# hamilton-thermostat-main.net
KiCad netlist of a schematic drawn in EAGLE
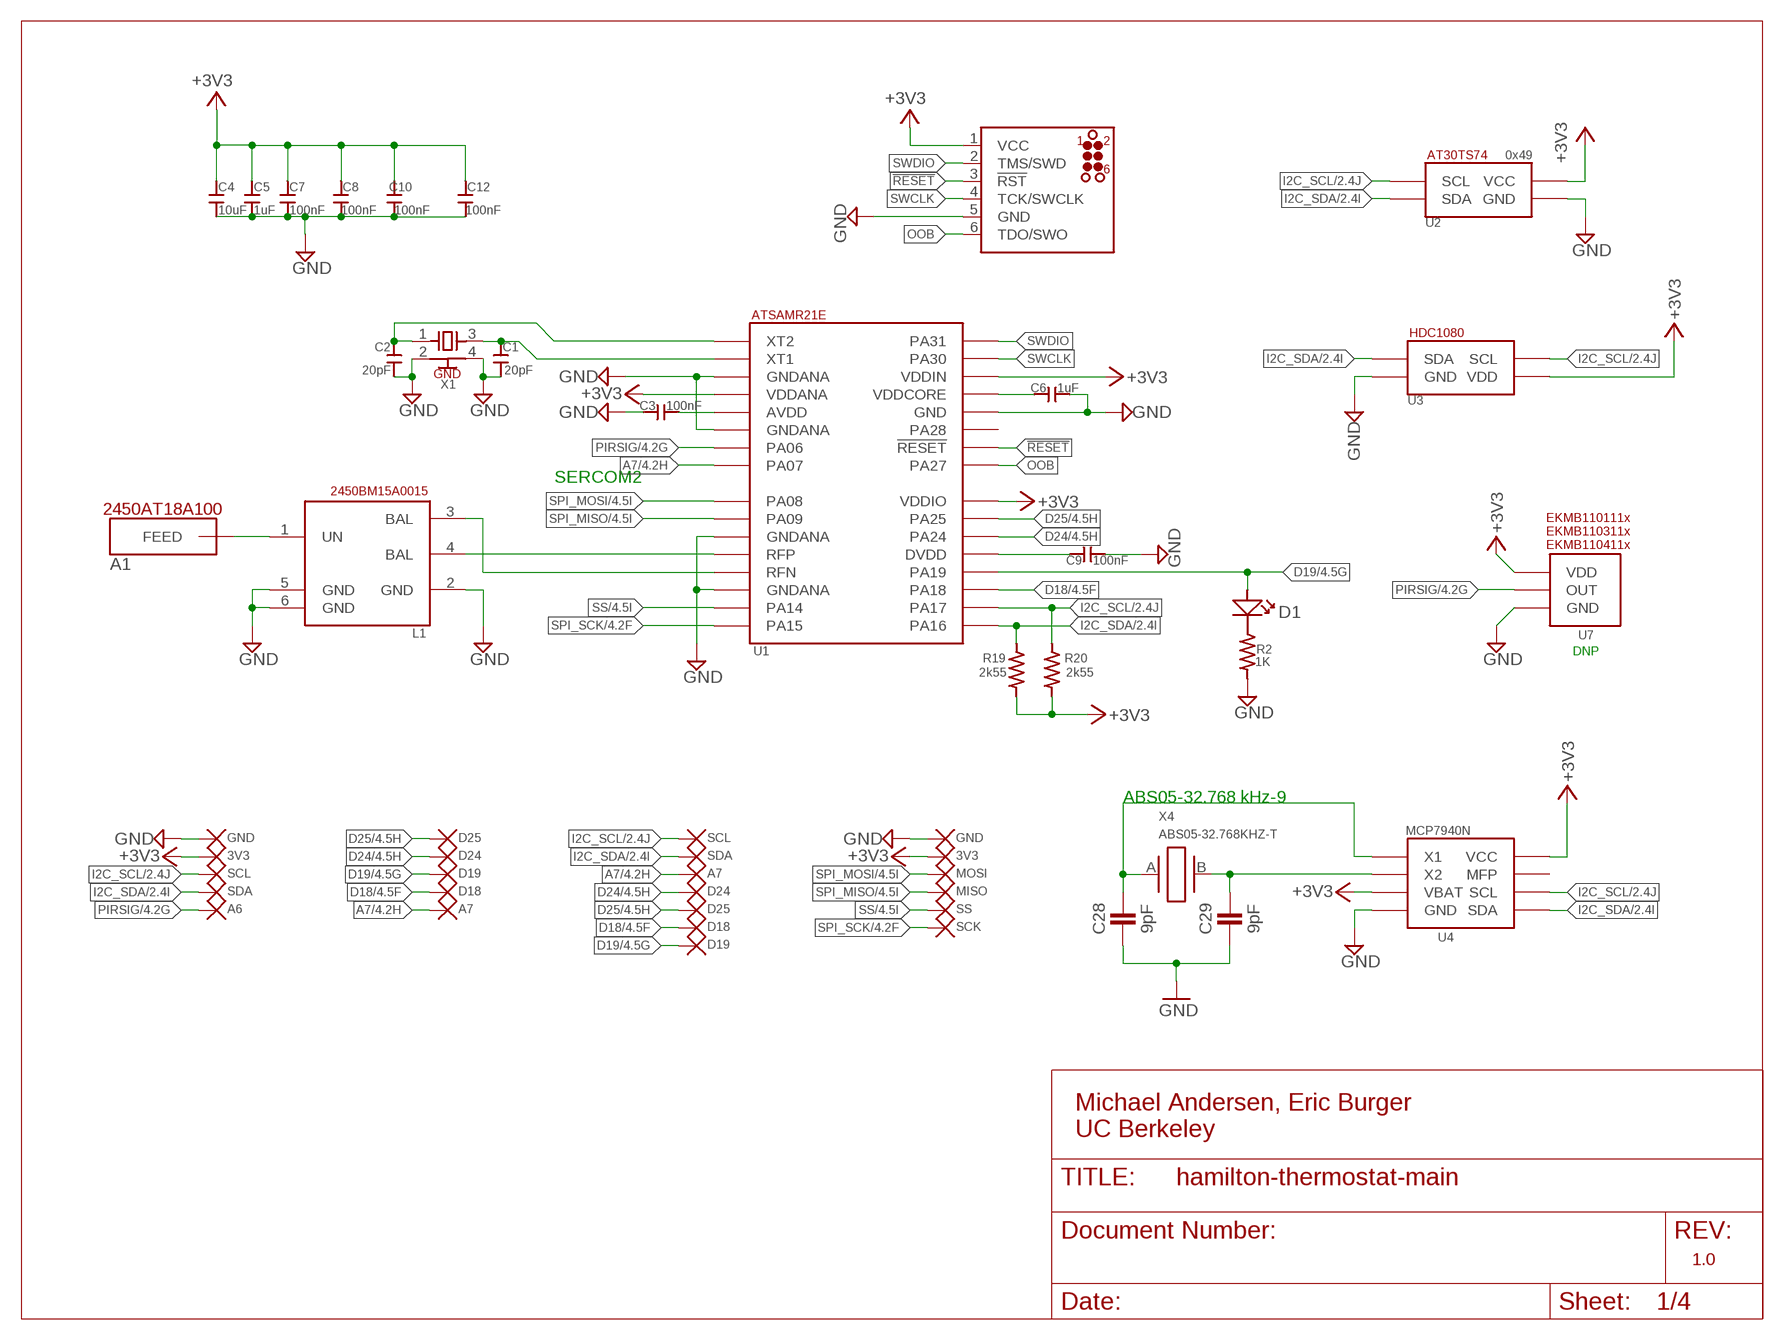
[diagram p0: schematic, sheet 1]
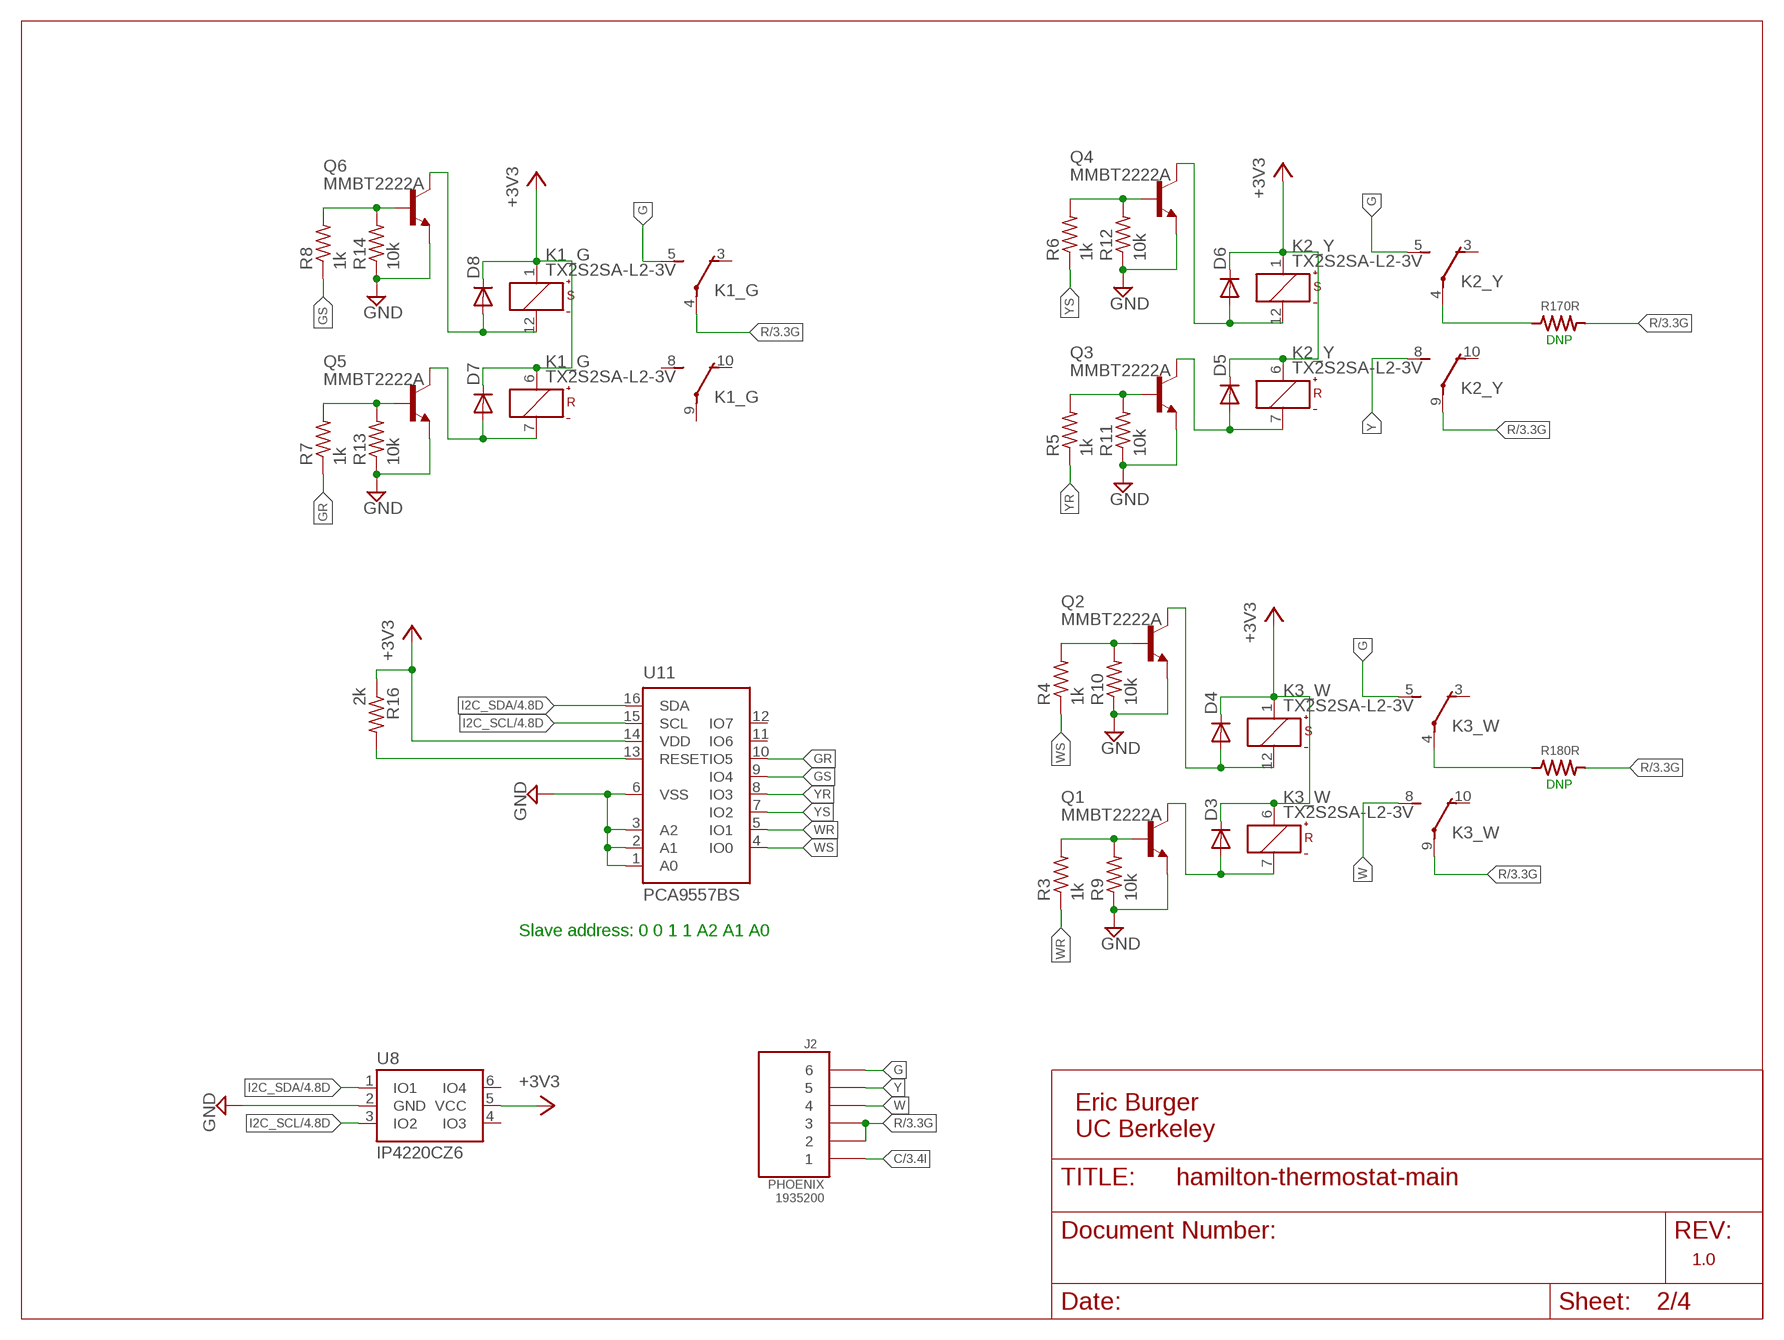
[diagram p1: schematic, sheet 2]
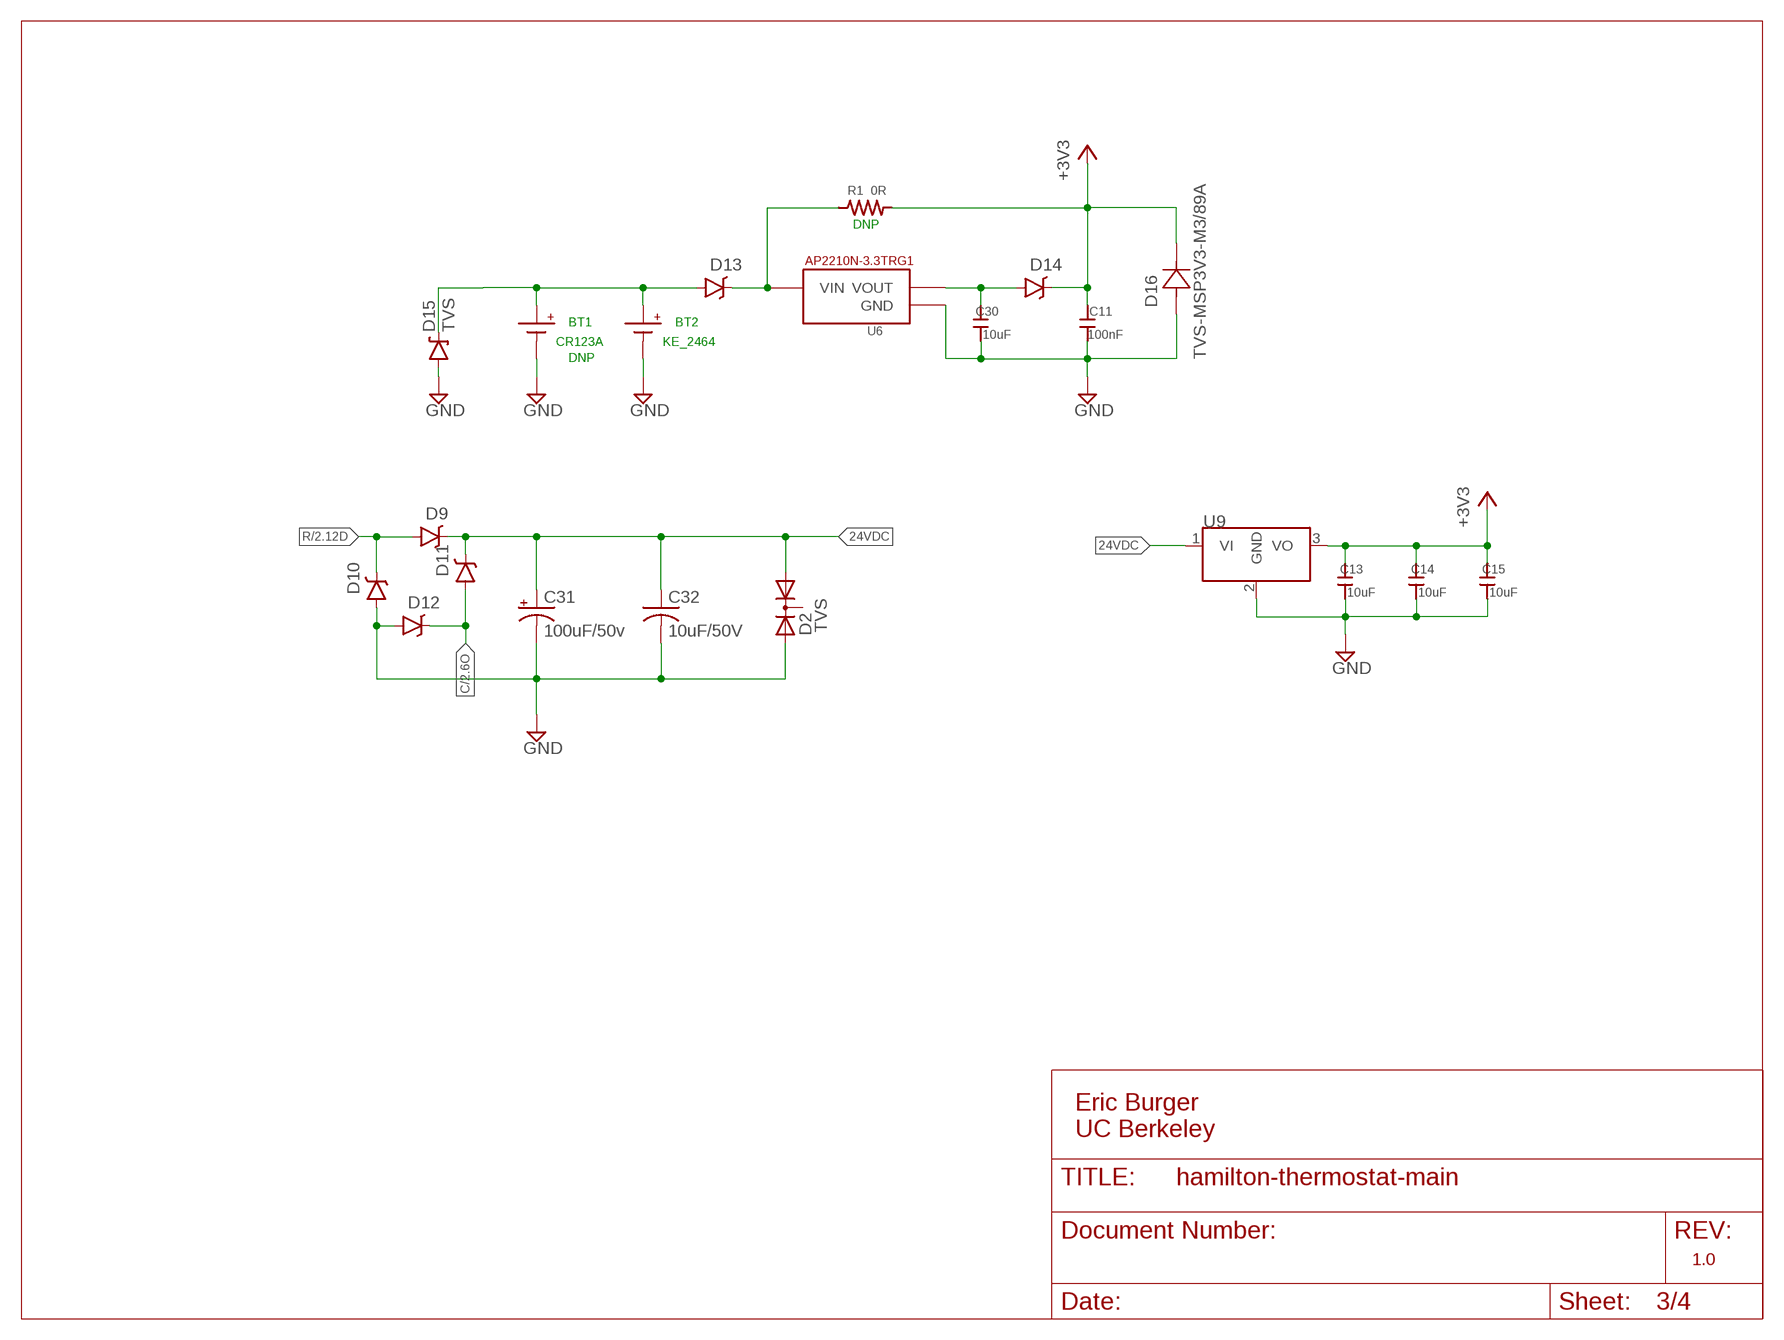
[diagram p2: schematic, sheet 3]
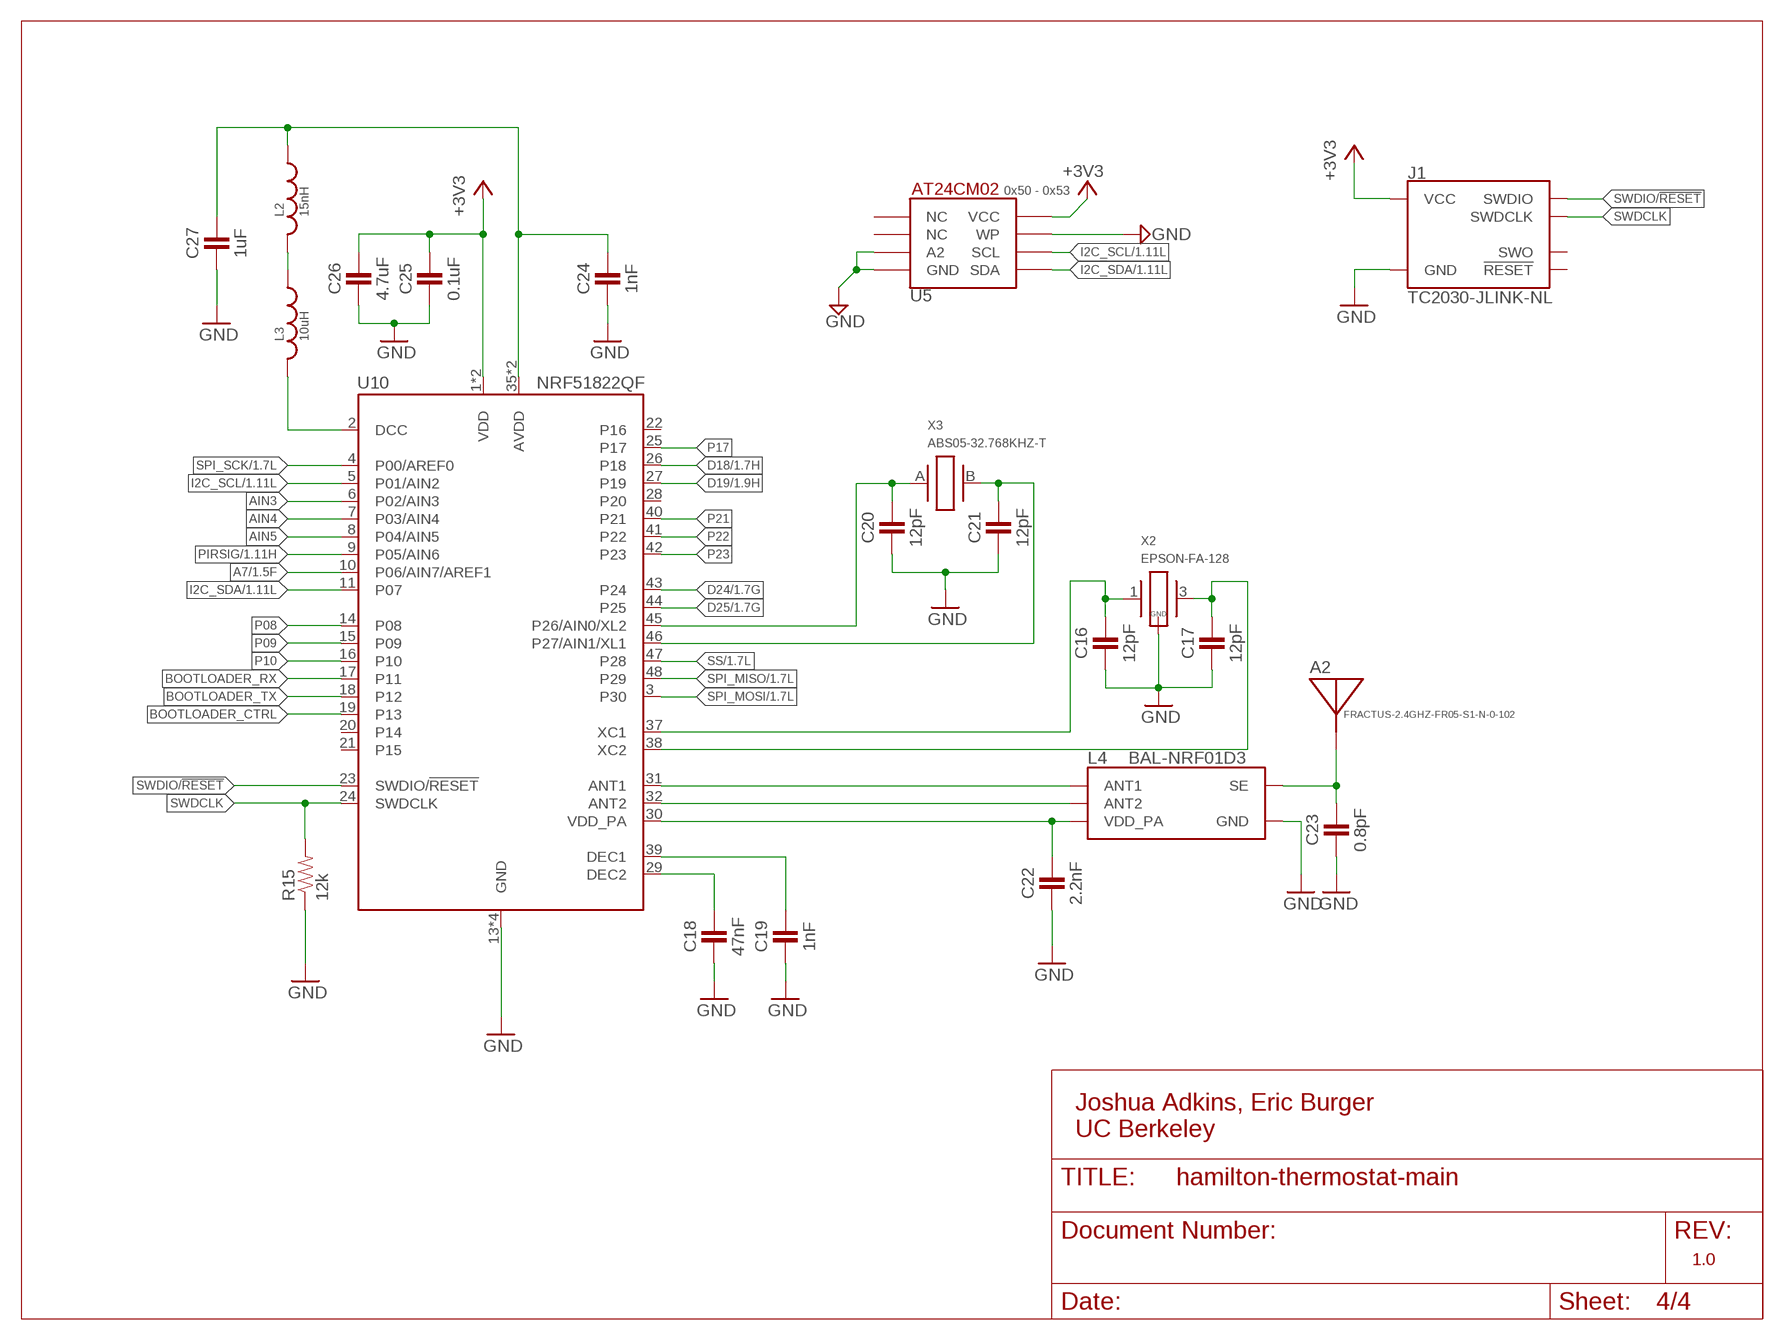
[diagram p3: schematic, sheet 4]

(export (version "E")
  (design (tool "Eeschema 10.0.6"))
  (components
    (comp (ref "BT1")
      (value "CR123A")
      (footprint "eagle-import:CR123A")
      (libsource (lib "eagle-import") (part "CR123A"))
    )
    (comp (ref "BT2")
      (value "BATTERY")
      (footprint "eagle-import:KE_2464")
      (libsource (lib "eagle-import") (part "BATTERY"))
    )
    (comp (ref "C11")
      (value "100nF")
      (footprint "eagle-import:S0402")
      (libsource (lib "eagle-import") (part "0603_CAPACITORSMALL"))
    )
    (comp (ref "C13")
      (value "10uF")
      (footprint "eagle-import:0805")
      (libsource (lib "eagle-import") (part "0805_CAPACITOR"))
    )
    (comp (ref "C14")
      (value "10uF")
      (footprint "eagle-import:0805")
      (libsource (lib "eagle-import") (part "0805_CAPACITOR"))
    )
    (comp (ref "C15")
      (value "10uF")
      (footprint "eagle-import:0805")
      (libsource (lib "eagle-import") (part "0805_CAPACITOR"))
    )
    (comp (ref "C30")
      (value "10uF")
      (footprint "eagle-import:0805")
      (libsource (lib "eagle-import") (part "0805_CAPACITOR"))
    )
    (comp (ref "C31")
      (value "100uF/50v")
      (footprint "eagle-import:NIC_10X10.5_CAP")
      (libsource (lib "eagle-import") (part "100UF-63V-20%(ELECT)"))
    )
    (comp (ref "C32")
      (value "10uF/50V")
      (footprint "eagle-import:C1206")
      (libsource (lib "eagle-import") (part "C-USC1206"))
    )
    (comp (ref "D2")
      (value "TVS")
      (footprint "eagle-import:SOT23")
      (libsource (lib "eagle-import") (part "DIODE-2AC|CASOT23"))
    )
    (comp (ref "D9")
      (value "MBRA140")
      (footprint "eagle-import:SMA-DIODE")
      (libsource (lib "eagle-import") (part "MBRA140"))
    )
    (comp (ref "D10")
      (value "MBRA140")
      (footprint "eagle-import:SMA-DIODE")
      (libsource (lib "eagle-import") (part "MBRA140"))
    )
    (comp (ref "D11")
      (value "MBRA140")
      (footprint "eagle-import:SMA-DIODE")
      (libsource (lib "eagle-import") (part "MBRA140"))
    )
    (comp (ref "D12")
      (value "MBRA140")
      (footprint "eagle-import:SMA-DIODE")
      (libsource (lib "eagle-import") (part "MBRA140"))
    )
    (comp (ref "D13")
      (value "MBRA140")
      (footprint "eagle-import:SMA-DIODE")
      (libsource (lib "eagle-import") (part "DIODE-SCHOTTKY-MBRA140"))
    )
    (comp (ref "D14")
      (value "MBRA140")
      (footprint "eagle-import:SMA-DIODE")
      (libsource (lib "eagle-import") (part "DIODE-SCHOTTKY-MBRA140"))
    )
    (comp (ref "D15")
      (value "TVS")
      (footprint "eagle-import:SMB-DIODE")
      (libsource (lib "eagle-import") (part "DIODE-ZENERSMB"))
    )
    (comp (ref "D16")
      (value "TVS-MSP3V3-M3/89A")
      (footprint "eagle-import:DIODE_MSP3V3")
      (fields (field (name "MANUFACTURER_PART_NUMBER") "MSP3V3M389A"))
      (libsource (lib "eagle-import") (part "MSP3V3-M3/89A"))
    )
    (comp (ref "R1")
      (value "0R")
      (footprint "eagle-import:S0402")
      (libsource (lib "eagle-import") (part "0603_RESISTORSMALL"))
    )
    (comp (ref "U6")
      (value "SOT23-3VREG")
      (footprint "eagle-import:SOT23")
      (libsource (lib "eagle-import") (part "SOT23-3VREG"))
    )
    (comp (ref "U9")
      (value "DCDC_OKI-78SR")
      (footprint "eagle-import:OKI-78SRH")
      (libsource (lib "eagle-import") (part "DCDC_OKI-78SR"))
    )
    (comp (ref "A1")
      (value "JOHANSON_ANTENNA2")
      (footprint "eagle-import:JOHANSON_ANTENNA2")
      (libsource (lib "eagle-import") (part "JOHANSON_ANTENNA2"))
    )
    (comp (ref "C1")
      (value "20pF")
      (footprint "eagle-import:S0402")
      (libsource (lib "eagle-import") (part "0603_CAPACITORSMALL"))
    )
    (comp (ref "C2")
      (value "20pF")
      (footprint "eagle-import:S0402")
      (libsource (lib "eagle-import") (part "0603_CAPACITORSMALL"))
    )
    (comp (ref "C3")
      (value "100nF")
      (footprint "eagle-import:S0402")
      (libsource (lib "eagle-import") (part "0603_CAPACITORSMALL"))
    )
    (comp (ref "C4")
      (value "10uF")
      (footprint "eagle-import:0805")
      (libsource (lib "eagle-import") (part "0805_CAPACITOR"))
    )
    (comp (ref "C5")
      (value "1uF")
      (footprint "eagle-import:S0402")
      (libsource (lib "eagle-import") (part "0603_CAPACITORSMALL"))
    )
    (comp (ref "C6")
      (value "1uF")
      (footprint "eagle-import:S0402")
      (libsource (lib "eagle-import") (part "0603_CAPACITORSMALL"))
    )
    (comp (ref "C7")
      (value "100nF")
      (footprint "eagle-import:S0402")
      (libsource (lib "eagle-import") (part "0603_CAPACITORSMALL"))
    )
    (comp (ref "C8")
      (value "100nF")
      (footprint "eagle-import:S0402")
      (libsource (lib "eagle-import") (part "0603_CAPACITORSMALL"))
    )
    (comp (ref "C9")
      (value "100nF")
      (footprint "eagle-import:S0402")
      (libsource (lib "eagle-import") (part "0603_CAPACITORSMALL"))
    )
    (comp (ref "C10")
      (value "100nF")
      (footprint "eagle-import:S0402")
      (libsource (lib "eagle-import") (part "0603_CAPACITORSMALL"))
    )
    (comp (ref "C12")
      (value "100nF")
      (footprint "eagle-import:S0402")
      (libsource (lib "eagle-import") (part "0603_CAPACITORSMALL"))
    )
    (comp (ref "C28")
      (value "9pF")
      (footprint "eagle-import:0402_CAP")
      (libsource (lib "eagle-import") (part "CAPACITOR"))
    )
    (comp (ref "C29")
      (value "9pF")
      (footprint "eagle-import:0402_CAP")
      (libsource (lib "eagle-import") (part "CAPACITOR"))
    )
    (comp (ref "D1")
      (value "DNP")
      (footprint "eagle-import:LINE_0603")
      (libsource (lib "eagle-import") (part "STATLEDLINE"))
    )
    (comp (ref "L1")
      (value "BALUN_JOHANSON")
      (footprint "eagle-import:BALUN_JOHANSON")
      (libsource (lib "eagle-import") (part "BALUN_JOHANSON"))
    )
    (comp (ref "R2")
      (value "1K")
      (footprint "eagle-import:S0402")
      (libsource (lib "eagle-import") (part "0603_RESISTORSMALL"))
    )
    (comp (ref "R19")
      (value "2k55")
      (footprint "eagle-import:S0402")
      (libsource (lib "eagle-import") (part "0603_RESISTORSMALL"))
    )
    (comp (ref "R20")
      (value "2k55")
      (footprint "eagle-import:S0402")
      (libsource (lib "eagle-import") (part "0603_RESISTORSMALL"))
    )
    (comp (ref "TP1")
      (value "D19")
      (footprint "eagle-import:TPP")
      (libsource (lib "eagle-import") (part "TP"))
    )
    (comp (ref "TP2")
      (value "D18")
      (footprint "eagle-import:TPP")
      (libsource (lib "eagle-import") (part "TP"))
    )
    (comp (ref "TP3")
      (value "A7")
      (footprint "eagle-import:TPP")
      (libsource (lib "eagle-import") (part "TP"))
    )
    (comp (ref "TP4")
      (value "D25")
      (footprint "eagle-import:TPP")
      (libsource (lib "eagle-import") (part "TP"))
    )
    (comp (ref "TP6")
      (value "GND")
      (footprint "eagle-import:TPP")
      (libsource (lib "eagle-import") (part "TP"))
    )
    (comp (ref "TP7")
      (value "SDA")
      (footprint "eagle-import:TPP")
      (libsource (lib "eagle-import") (part "TP"))
    )
    (comp (ref "TP8")
      (value "SCL")
      (footprint "eagle-import:TPP")
      (libsource (lib "eagle-import") (part "TP"))
    )
    (comp (ref "TP9")
      (value "SDA")
      (footprint "eagle-import:TPP")
      (libsource (lib "eagle-import") (part "TP"))
    )
    (comp (ref "TP10")
      (value "SCL")
      (footprint "eagle-import:TPP")
      (libsource (lib "eagle-import") (part "TP"))
    )
    (comp (ref "TP11")
      (value "3V3")
      (footprint "eagle-import:TPP")
      (libsource (lib "eagle-import") (part "TP"))
    )
    (comp (ref "TP12")
      (value "GND")
      (footprint "eagle-import:TPP")
      (libsource (lib "eagle-import") (part "TP"))
    )
    (comp (ref "TP13")
      (value "D24")
      (footprint "eagle-import:TPP")
      (libsource (lib "eagle-import") (part "TP"))
    )
    (comp (ref "TP14")
      (value "D25")
      (footprint "eagle-import:TPP")
      (libsource (lib "eagle-import") (part "TP"))
    )
    (comp (ref "TP15")
      (value "D24")
      (footprint "eagle-import:TPP")
      (libsource (lib "eagle-import") (part "TP"))
    )
    (comp (ref "TP16")
      (value "A6")
      (footprint "eagle-import:TPP")
      (libsource (lib "eagle-import") (part "TP"))
    )
    (comp (ref "TP17")
      (value "D18")
      (footprint "eagle-import:TPP")
      (libsource (lib "eagle-import") (part "TP"))
    )
    (comp (ref "TP18")
      (value "D19")
      (footprint "eagle-import:TPP")
      (libsource (lib "eagle-import") (part "TP"))
    )
    (comp (ref "TP19")
      (value "A7")
      (footprint "eagle-import:TPP")
      (libsource (lib "eagle-import") (part "TP"))
    )
    (comp (ref "TP20")
      (value "MOSI")
      (footprint "eagle-import:TPP")
      (libsource (lib "eagle-import") (part "TP"))
    )
    (comp (ref "TP21")
      (value "MISO")
      (footprint "eagle-import:TPP")
      (libsource (lib "eagle-import") (part "TP"))
    )
    (comp (ref "TP22")
      (value "SS")
      (footprint "eagle-import:TPP")
      (libsource (lib "eagle-import") (part "TP"))
    )
    (comp (ref "TP23")
      (value "SCK")
      (footprint "eagle-import:TPP")
      (libsource (lib "eagle-import") (part "TP"))
    )
    (comp (ref "TP24")
      (value "3V3")
      (footprint "eagle-import:TPP")
      (libsource (lib "eagle-import") (part "TP"))
    )
    (comp (ref "U$1")
      (value "JLINK_CONNECTWL")
      (footprint "eagle-import:TC2030-MCP")
      (libsource (lib "eagle-import") (part "JLINK_CONNECTWL"))
    )
    (comp (ref "U1")
      (value "SAMR21")
      (footprint "eagle-import:QFN32")
      (libsource (lib "eagle-import") (part "SAMR21"))
    )
    (comp (ref "U2")
      (value "AT30TS74")
      (footprint "eagle-import:4WLCSP")
      (libsource (lib "eagle-import") (part "AT30TS74"))
    )
    (comp (ref "U3")
      (value "HDC1080")
      (footprint "eagle-import:WSON_HDC1080")
      (libsource (lib "eagle-import") (part "HDC1080"))
    )
    (comp (ref "U4")
      (value "MCP7940N")
      (footprint "eagle-import:SO8")
      (libsource (lib "eagle-import") (part "MCP7940N"))
    )
    (comp (ref "U7")
      (value "PANASONIC_PIR")
      (footprint "eagle-import:PIR")
      (libsource (lib "eagle-import") (part "PANASONIC_PIR"))
    )
    (comp (ref "X1")
      (value "XTAL")
      (footprint "eagle-import:XTAL")
      (libsource (lib "eagle-import") (part "XTAL"))
    )
    (comp (ref "X4")
      (value "ABS05-32.768KHZ-T")
      (footprint "eagle-import:ABS05")
      (libsource (lib "eagle-import") (part "ABS05-32.768KHZ-T"))
    )
    (comp (ref "D3")
      (value "DIODE-DO-214AC")
      (footprint "eagle-import:DO-214AC")
      (libsource (lib "eagle-import") (part "DIODE-DO-214AC"))
    )
    (comp (ref "D4")
      (value "DIODE-DO-214AC")
      (footprint "eagle-import:DO-214AC")
      (libsource (lib "eagle-import") (part "DIODE-DO-214AC"))
    )
    (comp (ref "D5")
      (value "DIODE-DO-214AC")
      (footprint "eagle-import:DO-214AC")
      (libsource (lib "eagle-import") (part "DIODE-DO-214AC"))
    )
    (comp (ref "D6")
      (value "DIODE-DO-214AC")
      (footprint "eagle-import:DO-214AC")
      (libsource (lib "eagle-import") (part "DIODE-DO-214AC"))
    )
    (comp (ref "D7")
      (value "DIODE-DO-214AC")
      (footprint "eagle-import:DO-214AC")
      (libsource (lib "eagle-import") (part "DIODE-DO-214AC"))
    )
    (comp (ref "D8")
      (value "DIODE-DO-214AC")
      (footprint "eagle-import:DO-214AC")
      (libsource (lib "eagle-import") (part "DIODE-DO-214AC"))
    )
    (comp (ref "J2")
      (value "PHOENIX6W5MM")
      (footprint "eagle-import:PHOENIX6W5MM")
      (libsource (lib "eagle-import") (part "PHOENIX6W5MM"))
    )
    (comp (ref "K1_G")
      (value "TX2S2SA-L2-3V")
      (footprint "eagle-import:TX2SA-L2")
      (libsource (lib "eagle-import") (part "TX2?-L2-S2SA3V"))
    )
    (comp (ref "K2_Y")
      (value "TX2S2SA-L2-3V")
      (footprint "eagle-import:TX2SA-L2")
      (libsource (lib "eagle-import") (part "TX2?-L2-S2SA3V"))
    )
    (comp (ref "K3_W")
      (value "TX2S2SA-L2-3V")
      (footprint "eagle-import:TX2SA-L2")
      (libsource (lib "eagle-import") (part "TX2?-L2-S2SA3V"))
    )
    (comp (ref "Q1")
      (value "MMBT2222A")
      (footprint "eagle-import:SOT23-3")
      (libsource (lib "eagle-import") (part "TRANSISTOR_NPNMMBT2222A"))
    )
    (comp (ref "Q2")
      (value "MMBT2222A")
      (footprint "eagle-import:SOT23-3")
      (libsource (lib "eagle-import") (part "TRANSISTOR_NPNMMBT2222A"))
    )
    (comp (ref "Q3")
      (value "MMBT2222A")
      (footprint "eagle-import:SOT23-3")
      (libsource (lib "eagle-import") (part "TRANSISTOR_NPNMMBT2222A"))
    )
    (comp (ref "Q4")
      (value "MMBT2222A")
      (footprint "eagle-import:SOT23-3")
      (libsource (lib "eagle-import") (part "TRANSISTOR_NPNMMBT2222A"))
    )
    (comp (ref "Q5")
      (value "MMBT2222A")
      (footprint "eagle-import:SOT23-3")
      (libsource (lib "eagle-import") (part "TRANSISTOR_NPNMMBT2222A"))
    )
    (comp (ref "Q6")
      (value "MMBT2222A")
      (footprint "eagle-import:SOT23-3")
      (libsource (lib "eagle-import") (part "TRANSISTOR_NPNMMBT2222A"))
    )
    (comp (ref "R3")
      (value "1k")
      (footprint "eagle-import:R0402")
      (libsource (lib "eagle-import") (part "R-US_R0402"))
    )
    (comp (ref "R4")
      (value "1k")
      (footprint "eagle-import:R0402")
      (libsource (lib "eagle-import") (part "R-US_R0402"))
    )
    (comp (ref "R5")
      (value "1k")
      (footprint "eagle-import:R0402")
      (libsource (lib "eagle-import") (part "R-US_R0402"))
    )
    (comp (ref "R6")
      (value "1k")
      (footprint "eagle-import:R0402")
      (libsource (lib "eagle-import") (part "R-US_R0402"))
    )
    (comp (ref "R7")
      (value "1k")
      (footprint "eagle-import:R0402")
      (libsource (lib "eagle-import") (part "R-US_R0402"))
    )
    (comp (ref "R8")
      (value "1k")
      (footprint "eagle-import:R0402")
      (libsource (lib "eagle-import") (part "R-US_R0402"))
    )
    (comp (ref "R9")
      (value "10k")
      (footprint "eagle-import:R0402")
      (libsource (lib "eagle-import") (part "R-US_R0402"))
    )
    (comp (ref "R10")
      (value "10k")
      (footprint "eagle-import:R0402")
      (libsource (lib "eagle-import") (part "R-US_R0402"))
    )
    (comp (ref "R11")
      (value "10k")
      (footprint "eagle-import:R0402")
      (libsource (lib "eagle-import") (part "R-US_R0402"))
    )
    (comp (ref "R12")
      (value "10k")
      (footprint "eagle-import:R0402")
      (libsource (lib "eagle-import") (part "R-US_R0402"))
    )
    (comp (ref "R13")
      (value "10k")
      (footprint "eagle-import:R0402")
      (libsource (lib "eagle-import") (part "R-US_R0402"))
    )
    (comp (ref "R14")
      (value "10k")
      (footprint "eagle-import:R0402")
      (libsource (lib "eagle-import") (part "R-US_R0402"))
    )
    (comp (ref "R16")
      (value "2k")
      (footprint "eagle-import:R0402")
      (libsource (lib "eagle-import") (part "R-US_R0402"))
    )
    (comp (ref "R17")
      (value "0R")
      (footprint "eagle-import:S0402")
      (libsource (lib "eagle-import") (part "0603_RESISTORSMALL"))
    )
    (comp (ref "R18")
      (value "0R")
      (footprint "eagle-import:S0402")
      (libsource (lib "eagle-import") (part "0603_RESISTORSMALL"))
    )
    (comp (ref "U8")
      (value "IP4220CZ6")
      (footprint "eagle-import:SOT23-6")
      (libsource (lib "eagle-import") (part "IP4220CZ6SOT-23"))
    )
    (comp (ref "U11")
      (value "PCA9557BS")
      (footprint "eagle-import:HVQFN16_4X4")
      (fields (field (name "MPN") "PCA9557BS,118"))
      (libsource (lib "eagle-import") (part "PCA9557BS"))
    )
    (comp (ref "A2")
      (value "FRACTUS-2.4GHZ-FR05-S1-N-0-102")
      (footprint "eagle-import:FRACTUS-ANTENNA-FR05-S1-N-0-102")
      (libsource (lib "eagle-import") (part "FRACTUS-2.4GHZ-FR05-S1-N-0-102"))
    )
    (comp (ref "C16")
      (value "12pF")
      (footprint "eagle-import:0402_CAP")
      (libsource (lib "eagle-import") (part "CAPACITOR"))
    )
    (comp (ref "C17")
      (value "12pF")
      (footprint "eagle-import:0402_CAP")
      (libsource (lib "eagle-import") (part "CAPACITOR"))
    )
    (comp (ref "C18")
      (value "47nF")
      (footprint "eagle-import:0402_CAP")
      (libsource (lib "eagle-import") (part "CAPACITOR"))
    )
    (comp (ref "C19")
      (value "1nF")
      (footprint "eagle-import:0402_CAP")
      (libsource (lib "eagle-import") (part "CAPACITOR"))
    )
    (comp (ref "C20")
      (value "12pF")
      (footprint "eagle-import:0402_CAP")
      (libsource (lib "eagle-import") (part "CAPACITOR"))
    )
    (comp (ref "C21")
      (value "12pF")
      (footprint "eagle-import:0402_CAP")
      (libsource (lib "eagle-import") (part "CAPACITOR"))
    )
    (comp (ref "C22")
      (value "2.2nF")
      (footprint "eagle-import:0402_CAP")
      (libsource (lib "eagle-import") (part "CAPACITOR"))
    )
    (comp (ref "C23")
      (value "0.8pF")
      (footprint "eagle-import:0402_CAP")
      (libsource (lib "eagle-import") (part "CAPACITOR"))
    )
    (comp (ref "C24")
      (value "1nF")
      (footprint "eagle-import:0402_CAP")
      (libsource (lib "eagle-import") (part "CAPACITOR"))
    )
    (comp (ref "C25")
      (value "0.1uF")
      (footprint "eagle-import:0402_CAP")
      (libsource (lib "eagle-import") (part "CAPACITOR"))
    )
    (comp (ref "C26")
      (value "4.7uF")
      (footprint "eagle-import:0402_CAP")
      (libsource (lib "eagle-import") (part "CAPACITOR"))
    )
    (comp (ref "C27")
      (value "1uF")
      (footprint "eagle-import:0402_CAP")
      (libsource (lib "eagle-import") (part "CAPACITOR"))
    )
    (comp (ref "J1")
      (value "TC2030-JLINK-NL")
      (footprint "eagle-import:TC2030-IDC-NL")
      (libsource (lib "eagle-import") (part "TC2030-JLINK-NL"))
    )
    (comp (ref "L2")
      (value "15nH")
      (footprint "eagle-import:0402_CAP")
      (libsource (lib "eagle-import") (part "INDUCTOR0402"))
    )
    (comp (ref "L3")
      (value "10uH")
      (footprint "eagle-import:0603_CAP")
      (libsource (lib "eagle-import") (part "INDUCTOR0603"))
    )
    (comp (ref "L4")
      (value "BAL-NRF01D3")
      (footprint "eagle-import:BAL-NRF01D3")
      (libsource (lib "eagle-import") (part "BAL-NRF01D3"))
    )
    (comp (ref "R15")
      (value "12k")
      (footprint "eagle-import:0402_RES")
      (libsource (lib "eagle-import") (part "RESISTOR0402_RES"))
    )
    (comp (ref "U5")
      (value "AT24CM02")
      (footprint "eagle-import:SO8")
      (libsource (lib "eagle-import") (part "AT24CM02"))
    )
    (comp (ref "U10")
      (value "NRF51822QF")
      (footprint "eagle-import:QFN-48-6MM")
      (libsource (lib "eagle-import") (part "NRF51822QF"))
    )
    (comp (ref "X2")
      (value "EPSON-FA-128")
      (footprint "eagle-import:FA-128")
      (libsource (lib "eagle-import") (part "EPSON-FA-128"))
    )
    (comp (ref "X3")
      (value "ABS05-32.768KHZ-T")
      (footprint "eagle-import:ABS05")
      (libsource (lib "eagle-import") (part "ABS05-32.768KHZ-T"))
    )
  )
  (nets
    (net (code "1") (name "+3V3") (class "Default")
      (node (ref "C10") (pin "P$1") (pinfunction "P$1_P$1") (pintype "passive"))
      (node (ref "C11") (pin "P$1") (pinfunction "P$1_P$1") (pintype "passive"))
      (node (ref "C12") (pin "P$1") (pinfunction "P$1_P$1") (pintype "passive"))
      (node (ref "C13") (pin "2") (pinfunction "P$2_2") (pintype "passive"))
      (node (ref "C14") (pin "2") (pinfunction "P$2_2") (pintype "passive"))
      (node (ref "C15") (pin "2") (pinfunction "P$2_2") (pintype "passive"))
      (node (ref "C25") (pin "1") (pinfunction "1_1") (pintype "bidirectional"))
      (node (ref "C26") (pin "1") (pinfunction "1_1") (pintype "bidirectional"))
      (node (ref "C4") (pin "2") (pinfunction "P$2_2") (pintype "passive"))
      (node (ref "C5") (pin "P$2") (pinfunction "P$2_P$2") (pintype "passive"))
      (node (ref "C7") (pin "P$1") (pinfunction "P$1_P$1") (pintype "passive"))
      (node (ref "C8") (pin "P$1") (pinfunction "P$1_P$1") (pintype "passive"))
      (node (ref "D14") (pin "C") (pinfunction "C_C") (pintype "passive"))
      (node (ref "D16") (pin "1") (pinfunction "12_1") (pintype "passive"))
      (node (ref "D3") (pin "C") (pinfunction "C_C") (pintype "passive"))
      (node (ref "D4") (pin "C") (pinfunction "C_C") (pintype "passive"))
      (node (ref "D5") (pin "C") (pinfunction "C_C") (pintype "passive"))
      (node (ref "D6") (pin "C") (pinfunction "C_C") (pintype "passive"))
      (node (ref "D7") (pin "C") (pinfunction "C_C") (pintype "passive"))
      (node (ref "D8") (pin "C") (pinfunction "C_C") (pintype "passive"))
      (node (ref "J1") (pin "1") (pinfunction "VCC_1") (pintype "bidirectional"))
      (node (ref "K1_G") (pin "1") (pinfunction "+_1") (pintype "passive"))
      (node (ref "K1_G") (pin "6") (pinfunction "+_6") (pintype "passive"))
      (node (ref "K2_Y") (pin "1") (pinfunction "+_1") (pintype "passive"))
      (node (ref "K2_Y") (pin "6") (pinfunction "+_6") (pintype "passive"))
      (node (ref "K3_W") (pin "1") (pinfunction "+_1") (pintype "passive"))
      (node (ref "K3_W") (pin "6") (pinfunction "+_6") (pintype "passive"))
      (node (ref "R1") (pin "P$1") (pinfunction "P$1_P$1") (pintype "passive"))
      (node (ref "R16") (pin "1") (pinfunction "1_1") (pintype "passive"))
      (node (ref "R19") (pin "P$1") (pinfunction "P$1_P$1") (pintype "passive"))
      (node (ref "R20") (pin "P$1") (pinfunction "P$1_P$1") (pintype "passive"))
      (node (ref "TP11") (pin "P$1") (pinfunction "P$1_P$1") (pintype "bidirectional"))
      (node (ref "TP24") (pin "P$1") (pinfunction "P$1_P$1") (pintype "bidirectional"))
      (node (ref "U$1") (pin "1") (pinfunction "VCC_1") (pintype "passive"))
      (node (ref "U1") (pin "24") (pinfunction "VDDIO_24") (pintype "bidirectional"))
      (node (ref "U1") (pin "30") (pinfunction "VDDIN_30") (pintype "bidirectional"))
      (node (ref "U1") (pin "4") (pinfunction "VDDANA_4") (pintype "bidirectional"))
      (node (ref "U10") (pin "1") (pinfunction "VDD_1") (pintype "bidirectional"))
      (node (ref "U10") (pin "12") (pinfunction "VDD_12") (pintype "bidirectional"))
      (node (ref "U11") (pin "14") (pinfunction "VDD_14") (pintype "power_in"))
      (node (ref "U2") (pin "A1") (pinfunction "VCC_A1") (pintype "bidirectional"))
      (node (ref "U3") (pin "5") (pinfunction "VDD_5") (pintype "bidirectional"))
      (node (ref "U4") (pin "3") (pinfunction "VBAT_3") (pintype "bidirectional"))
      (node (ref "U4") (pin "8") (pinfunction "VCC_8") (pintype "bidirectional"))
      (node (ref "U5") (pin "8") (pinfunction "VCC_8") (pintype "bidirectional"))
      (node (ref "U7") (pin "VDD") (pinfunction "VDD_VDD") (pintype "bidirectional"))
      (node (ref "U8") (pin "5") (pinfunction "VCC_5") (pintype "bidirectional"))
      (node (ref "U9") (pin "3") (pinfunction "VO_3") (pintype "bidirectional"))
    )
    (net (code "2") (name "24VDC") (class "Default")
      (node (ref "C31") (pin "+") (pinfunction "+_+") (pintype "passive"))
      (node (ref "C32") (pin "1") (pinfunction "1_1") (pintype "passive"))
      (node (ref "D11") (pin "C") (pinfunction "C_C") (pintype "passive"))
      (node (ref "D2") (pin "1") (pinfunction "A1_1") (pintype "passive"))
      (node (ref "D9") (pin "C") (pinfunction "C_C") (pintype "passive"))
      (node (ref "U9") (pin "1") (pinfunction "VI_1") (pintype "bidirectional"))
    )
    (net (code "3") (name "A7") (class "Default")
      (node (ref "TP19") (pin "P$1") (pinfunction "P$1_P$1") (pintype "bidirectional"))
      (node (ref "TP3") (pin "P$1") (pinfunction "P$1_P$1") (pintype "bidirectional"))
      (node (ref "U1") (pin "8") (pinfunction "PA07_8") (pintype "bidirectional"))
      (node (ref "U10") (pin "10") (pinfunction "P06/AIN7/AREF1_10") (pintype "bidirectional"))
    )
    (net (code "4") (name "AIN3") (class "Default")
      (node (ref "U10") (pin "6") (pinfunction "P02/AIN3_6") (pintype "bidirectional"))
    )
    (net (code "5") (name "AIN4") (class "Default")
      (node (ref "U10") (pin "7") (pinfunction "P03/AIN4_7") (pintype "bidirectional"))
    )
    (net (code "6") (name "AIN5") (class "Default")
      (node (ref "U10") (pin "8") (pinfunction "P04/AIN5_8") (pintype "bidirectional"))
    )
    (net (code "7") (name "BOOTLOADER_CTRL") (class "Default")
      (node (ref "U10") (pin "19") (pinfunction "P13_19") (pintype "bidirectional"))
    )
    (net (code "8") (name "BOOTLOADER_RX") (class "Default")
      (node (ref "U10") (pin "17") (pinfunction "P11_17") (pintype "bidirectional"))
    )
    (net (code "9") (name "BOOTLOADER_TX") (class "Default")
      (node (ref "U10") (pin "18") (pinfunction "P12_18") (pintype "bidirectional"))
    )
    (net (code "10") (name "C") (class "Default")
      (node (ref "D11") (pin "A") (pinfunction "A_A") (pintype "passive"))
      (node (ref "D12") (pin "C") (pinfunction "C_C") (pintype "passive"))
      (node (ref "J2") (pin "P$1") (pinfunction "1_P$1") (pintype "bidirectional"))
    )
    (net (code "11") (name "D18") (class "Default")
      (node (ref "TP17") (pin "P$1") (pinfunction "P$1_P$1") (pintype "bidirectional"))
      (node (ref "TP2") (pin "P$1") (pinfunction "P$1_P$1") (pintype "bidirectional"))
      (node (ref "U1") (pin "19") (pinfunction "PA18_19") (pintype "bidirectional"))
      (node (ref "U10") (pin "26") (pinfunction "P18_26") (pintype "bidirectional"))
    )
    (net (code "12") (name "D19") (class "Default")
      (node (ref "D1") (pin "P") (pinfunction "+_P") (pintype "passive"))
      (node (ref "TP1") (pin "P$1") (pinfunction "P$1_P$1") (pintype "bidirectional"))
      (node (ref "TP18") (pin "P$1") (pinfunction "P$1_P$1") (pintype "bidirectional"))
      (node (ref "U1") (pin "20") (pinfunction "PA19_20") (pintype "bidirectional"))
      (node (ref "U10") (pin "27") (pinfunction "P19_27") (pintype "bidirectional"))
    )
    (net (code "13") (name "D24") (class "Default")
      (node (ref "TP13") (pin "P$1") (pinfunction "P$1_P$1") (pintype "bidirectional"))
      (node (ref "TP15") (pin "P$1") (pinfunction "P$1_P$1") (pintype "bidirectional"))
      (node (ref "U1") (pin "22") (pinfunction "PA24_22") (pintype "bidirectional"))
      (node (ref "U10") (pin "43") (pinfunction "P24_43") (pintype "bidirectional"))
    )
    (net (code "14") (name "D25") (class "Default")
      (node (ref "TP14") (pin "P$1") (pinfunction "P$1_P$1") (pintype "bidirectional"))
      (node (ref "TP4") (pin "P$1") (pinfunction "P$1_P$1") (pintype "bidirectional"))
      (node (ref "U1") (pin "23") (pinfunction "PA25_23") (pintype "bidirectional"))
      (node (ref "U10") (pin "44") (pinfunction "P25_44") (pintype "bidirectional"))
    )
    (net (code "15") (name "G") (class "Default")
      (node (ref "J2") (pin "P$6") (pinfunction "6_P$6") (pintype "bidirectional"))
      (node (ref "K1_G") (pin "5") (pinfunction "S_5") (pintype "passive"))
      (node (ref "K2_Y") (pin "5") (pinfunction "S_5") (pintype "passive"))
      (node (ref "K3_W") (pin "5") (pinfunction "S_5") (pintype "passive"))
    )
    (net (code "16") (name "GND") (class "Default")
      (node (ref "BT1") (pin "NEG") (pinfunction "-_NEG") (pintype "bidirectional"))
      (node (ref "BT2") (pin "NEG") (pinfunction "-_NEG") (pintype "bidirectional"))
      (node (ref "C1") (pin "P$1") (pinfunction "P$1_P$1") (pintype "passive"))
      (node (ref "C10") (pin "P$2") (pinfunction "P$2_P$2") (pintype "passive"))
      (node (ref "C11") (pin "P$2") (pinfunction "P$2_P$2") (pintype "passive"))
      (node (ref "C12") (pin "P$2") (pinfunction "P$2_P$2") (pintype "passive"))
      (node (ref "C13") (pin "1") (pinfunction "P$1_1") (pintype "passive"))
      (node (ref "C14") (pin "1") (pinfunction "P$1_1") (pintype "passive"))
      (node (ref "C15") (pin "1") (pinfunction "P$1_1") (pintype "passive"))
      (node (ref "C16") (pin "2") (pinfunction "2_2") (pintype "bidirectional"))
      (node (ref "C17") (pin "2") (pinfunction "2_2") (pintype "bidirectional"))
      (node (ref "C18") (pin "2") (pinfunction "2_2") (pintype "bidirectional"))
      (node (ref "C19") (pin "2") (pinfunction "2_2") (pintype "bidirectional"))
      (node (ref "C2") (pin "P$1") (pinfunction "P$1_P$1") (pintype "passive"))
      (node (ref "C20") (pin "2") (pinfunction "2_2") (pintype "bidirectional"))
      (node (ref "C21") (pin "2") (pinfunction "2_2") (pintype "bidirectional"))
      (node (ref "C22") (pin "2") (pinfunction "2_2") (pintype "bidirectional"))
      (node (ref "C23") (pin "2") (pinfunction "2_2") (pintype "bidirectional"))
      (node (ref "C24") (pin "2") (pinfunction "2_2") (pintype "bidirectional"))
      (node (ref "C25") (pin "2") (pinfunction "2_2") (pintype "bidirectional"))
      (node (ref "C26") (pin "2") (pinfunction "2_2") (pintype "bidirectional"))
      (node (ref "C27") (pin "2") (pinfunction "2_2") (pintype "bidirectional"))
      (node (ref "C28") (pin "2") (pinfunction "2_2") (pintype "bidirectional"))
      (node (ref "C29") (pin "2") (pinfunction "2_2") (pintype "bidirectional"))
      (node (ref "C3") (pin "P$2") (pinfunction "P$2_P$2") (pintype "passive"))
      (node (ref "C30") (pin "1") (pinfunction "P$1_1") (pintype "passive"))
      (node (ref "C31") (pin "-") (pinfunction "-_-") (pintype "passive"))
      (node (ref "C32") (pin "2") (pinfunction "2_2") (pintype "passive"))
      (node (ref "C4") (pin "1") (pinfunction "P$1_1") (pintype "passive"))
      (node (ref "C5") (pin "P$1") (pinfunction "P$1_P$1") (pintype "passive"))
      (node (ref "C6") (pin "P$1") (pinfunction "P$1_P$1") (pintype "passive"))
      (node (ref "C7") (pin "P$2") (pinfunction "P$2_P$2") (pintype "passive"))
      (node (ref "C8") (pin "P$2") (pinfunction "P$2_P$2") (pintype "passive"))
      (node (ref "C9") (pin "P$1") (pinfunction "P$1_P$1") (pintype "passive"))
      (node (ref "D10") (pin "A") (pinfunction "A_A") (pintype "passive"))
      (node (ref "D12") (pin "A") (pinfunction "A_A") (pintype "passive"))
      (node (ref "D15") (pin "A") (pinfunction "A_A") (pintype "passive"))
      (node (ref "D16") (pin "2") (pinfunction "21_2") (pintype "passive"))
      (node (ref "D2") (pin "2") (pinfunction "A2_2") (pintype "passive"))
      (node (ref "J1") (pin "5") (pinfunction "GND_5") (pintype "bidirectional"))
      (node (ref "L1") (pin "2") (pinfunction "GND_2") (pintype "bidirectional"))
      (node (ref "L1") (pin "5") (pinfunction "GND_5") (pintype "bidirectional"))
      (node (ref "L1") (pin "6") (pinfunction "GND_6") (pintype "bidirectional"))
      (node (ref "L4") (pin "GND") (pinfunction "GND_GND") (pintype "bidirectional"))
      (node (ref "Q1") (pin "2") (pinfunction "E_2") (pintype "passive"))
      (node (ref "Q2") (pin "2") (pinfunction "E_2") (pintype "passive"))
      (node (ref "Q3") (pin "2") (pinfunction "E_2") (pintype "passive"))
      (node (ref "Q4") (pin "2") (pinfunction "E_2") (pintype "passive"))
      (node (ref "Q5") (pin "2") (pinfunction "E_2") (pintype "passive"))
      (node (ref "Q6") (pin "2") (pinfunction "E_2") (pintype "passive"))
      (node (ref "R10") (pin "1") (pinfunction "1_1") (pintype "passive"))
      (node (ref "R11") (pin "1") (pinfunction "1_1") (pintype "passive"))
      (node (ref "R12") (pin "1") (pinfunction "1_1") (pintype "passive"))
      (node (ref "R13") (pin "1") (pinfunction "1_1") (pintype "passive"))
      (node (ref "R14") (pin "1") (pinfunction "1_1") (pintype "passive"))
      (node (ref "R15") (pin "1") (pinfunction "1_1") (pintype "passive"))
      (node (ref "R2") (pin "P$1") (pinfunction "P$1_P$1") (pintype "passive"))
      (node (ref "R9") (pin "1") (pinfunction "1_1") (pintype "passive"))
      (node (ref "TP12") (pin "P$1") (pinfunction "P$1_P$1") (pintype "bidirectional"))
      (node (ref "TP6") (pin "P$1") (pinfunction "P$1_P$1") (pintype "bidirectional"))
      (node (ref "U$1") (pin "5") (pinfunction "GND_5") (pintype "power_in"))
      (node (ref "U1") (pin "11") (pinfunction "GNDANA_11") (pintype "bidirectional"))
      (node (ref "U1") (pin "14") (pinfunction "GNDANA_14") (pintype "bidirectional"))
      (node (ref "U1") (pin "28") (pinfunction "GND_28") (pintype "bidirectional"))
      (node (ref "U1") (pin "3") (pinfunction "GNDANA_3") (pintype "bidirectional"))
      (node (ref "U1") (pin "6") (pinfunction "GNDANA_6") (pintype "bidirectional"))
      (node (ref "U10") (pin "13") (pinfunction "GND_13") (pintype "bidirectional"))
      (node (ref "U10") (pin "33") (pinfunction "GND_33") (pintype "bidirectional"))
      (node (ref "U10") (pin "34") (pinfunction "GND_34") (pintype "bidirectional"))
      (node (ref "U10") (pin "GND") (pinfunction "GND_GND") (pintype "bidirectional"))
      (node (ref "U11") (pin "1") (pinfunction "A0_1") (pintype "bidirectional"))
      (node (ref "U11") (pin "2") (pinfunction "A1_2") (pintype "bidirectional"))
      (node (ref "U11") (pin "3") (pinfunction "A2_3") (pintype "bidirectional"))
      (node (ref "U11") (pin "6") (pinfunction "VSS_6") (pintype "power_in"))
      (node (ref "U2") (pin "A2") (pinfunction "GND_A2") (pintype "bidirectional"))
      (node (ref "U3") (pin "2") (pinfunction "GND_2") (pintype "bidirectional"))
      (node (ref "U4") (pin "4") (pinfunction "GND_4") (pintype "bidirectional"))
      (node (ref "U5") (pin "3") (pinfunction "A2_3") (pintype "bidirectional"))
      (node (ref "U5") (pin "4") (pinfunction "GND_4") (pintype "bidirectional"))
      (node (ref "U5") (pin "7") (pinfunction "WP_7") (pintype "bidirectional"))
      (node (ref "U6") (pin "1") (pinfunction "GND_1") (pintype "bidirectional"))
      (node (ref "U7") (pin "GND") (pinfunction "GND_GND") (pintype "bidirectional"))
      (node (ref "U8") (pin "2") (pinfunction "GND_2") (pintype "bidirectional"))
      (node (ref "U9") (pin "2") (pinfunction "GND_2") (pintype "bidirectional"))
      (node (ref "X1") (pin "2") (pinfunction "GND_2") (pintype "power_in"))
      (node (ref "X1") (pin "4") (pinfunction "GND_4") (pintype "power_in"))
      (node (ref "X2") (pin "2") (pinfunction "GND_2") (pintype "bidirectional"))
      (node (ref "X2") (pin "4") (pinfunction "GND_4") (pintype "bidirectional"))
    )
    (net (code "17") (name "GR") (class "Default")
      (node (ref "R7") (pin "1") (pinfunction "1_1") (pintype "passive"))
      (node (ref "U11") (pin "10") (pinfunction "IO5_10") (pintype "bidirectional"))
    )
    (net (code "18") (name "GS") (class "Default")
      (node (ref "R8") (pin "1") (pinfunction "1_1") (pintype "passive"))
      (node (ref "U11") (pin "9") (pinfunction "IO4_9") (pintype "bidirectional"))
    )
    (net (code "19") (name "I2C_SCL") (class "Default")
      (node (ref "R20") (pin "P$2") (pinfunction "P$2_P$2") (pintype "passive"))
      (node (ref "TP10") (pin "P$1") (pinfunction "P$1_P$1") (pintype "bidirectional"))
      (node (ref "TP8") (pin "P$1") (pinfunction "P$1_P$1") (pintype "bidirectional"))
      (node (ref "U1") (pin "18") (pinfunction "PA17_18") (pintype "bidirectional"))
      (node (ref "U10") (pin "5") (pinfunction "P01/AIN2_5") (pintype "bidirectional"))
      (node (ref "U11") (pin "15") (pinfunction "SCL_15") (pintype "input"))
      (node (ref "U2") (pin "B2") (pinfunction "SCL_B2") (pintype "bidirectional"))
      (node (ref "U3") (pin "6") (pinfunction "SCL_6") (pintype "bidirectional"))
      (node (ref "U4") (pin "6") (pinfunction "SCL_6") (pintype "bidirectional"))
      (node (ref "U5") (pin "6") (pinfunction "SCL_6") (pintype "bidirectional"))
      (node (ref "U8") (pin "3") (pinfunction "IO2_3") (pintype "bidirectional"))
    )
    (net (code "20") (name "I2C_SDA") (class "Default")
      (node (ref "R19") (pin "P$2") (pinfunction "P$2_P$2") (pintype "passive"))
      (node (ref "TP7") (pin "P$1") (pinfunction "P$1_P$1") (pintype "bidirectional"))
      (node (ref "TP9") (pin "P$1") (pinfunction "P$1_P$1") (pintype "bidirectional"))
      (node (ref "U1") (pin "17") (pinfunction "PA16_17") (pintype "bidirectional"))
      (node (ref "U10") (pin "11") (pinfunction "P07_11") (pintype "bidirectional"))
      (node (ref "U11") (pin "16") (pinfunction "SDA_16") (pintype "input"))
      (node (ref "U2") (pin "B1") (pinfunction "SDA_B1") (pintype "bidirectional"))
      (node (ref "U3") (pin "1") (pinfunction "SDA_1") (pintype "bidirectional"))
      (node (ref "U4") (pin "5") (pinfunction "SDA_5") (pintype "bidirectional"))
      (node (ref "U5") (pin "5") (pinfunction "SDA_5") (pintype "bidirectional"))
      (node (ref "U8") (pin "1") (pinfunction "IO1_1") (pintype "bidirectional"))
    )
    (net (code "21") (name "Net-(A2-ANTENNA)") (class "Default")
      (node (ref "A2") (pin "1") (pinfunction "ANTENNA_1") (pintype "bidirectional"))
      (node (ref "C23") (pin "1") (pinfunction "1_1") (pintype "bidirectional"))
      (node (ref "L4") (pin "SE") (pinfunction "SE_SE") (pintype "bidirectional"))
    )
    (net (code "22") (name "Net-(BT1-+)") (class "Default")
      (node (ref "BT1") (pin "POS") (pinfunction "+_POS") (pintype "bidirectional"))
      (node (ref "BT2") (pin "POS") (pinfunction "+_POS") (pintype "bidirectional"))
      (node (ref "D13") (pin "A") (pinfunction "A_A") (pintype "passive"))
      (node (ref "D15") (pin "C") (pinfunction "C_C") (pintype "passive"))
    )
    (net (code "23") (name "Net-(C24-Pad1)") (class "Default")
      (node (ref "C24") (pin "1") (pinfunction "1_1") (pintype "bidirectional"))
      (node (ref "C27") (pin "1") (pinfunction "1_1") (pintype "bidirectional"))
      (node (ref "L2") (pin "1") (pinfunction "1_1") (pintype "bidirectional"))
      (node (ref "U10") (pin "35") (pinfunction "AVDD_35") (pintype "bidirectional"))
      (node (ref "U10") (pin "36") (pinfunction "AVDD_36") (pintype "bidirectional"))
    )
    (net (code "24") (name "Net-(C30-P$2)") (class "Default")
      (node (ref "C30") (pin "2") (pinfunction "P$2_2") (pintype "passive"))
      (node (ref "D14") (pin "A") (pinfunction "A_A") (pintype "passive"))
      (node (ref "U6") (pin "2") (pinfunction "VOUT_2") (pintype "bidirectional"))
    )
    (net (code "25") (name "Net-(D1--)") (class "Default")
      (node (ref "D1") (pin "N") (pinfunction "-_N") (pintype "passive"))
      (node (ref "R2") (pin "P$2") (pinfunction "P$2_P$2") (pintype "passive"))
    )
    (net (code "26") (name "Net-(K1_GC--)") (class "Default")
      (node (ref "D7") (pin "A") (pinfunction "A_A") (pintype "passive"))
      (node (ref "K1_G") (pin "7") (pinfunction "-_7") (pintype "passive"))
      (node (ref "Q5") (pin "3") (pinfunction "C_3") (pintype "passive"))
    )
    (net (code "27") (name "Net-(K1_GD--)") (class "Default")
      (node (ref "D8") (pin "A") (pinfunction "A_A") (pintype "passive"))
      (node (ref "K1_G") (pin "12") (pinfunction "-_12") (pintype "passive"))
      (node (ref "Q6") (pin "3") (pinfunction "C_3") (pintype "passive"))
    )
    (net (code "28") (name "Net-(K2_YA-P)") (class "Default")
      (node (ref "K2_Y") (pin "4") (pinfunction "P_4") (pintype "passive"))
      (node (ref "R17") (pin "P$2") (pinfunction "P$2_P$2") (pintype "passive"))
    )
    (net (code "29") (name "Net-(K2_YC--)") (class "Default")
      (node (ref "D5") (pin "A") (pinfunction "A_A") (pintype "passive"))
      (node (ref "K2_Y") (pin "7") (pinfunction "-_7") (pintype "passive"))
      (node (ref "Q3") (pin "3") (pinfunction "C_3") (pintype "passive"))
    )
    (net (code "30") (name "Net-(K2_YD--)") (class "Default")
      (node (ref "D6") (pin "A") (pinfunction "A_A") (pintype "passive"))
      (node (ref "K2_Y") (pin "12") (pinfunction "-_12") (pintype "passive"))
      (node (ref "Q4") (pin "3") (pinfunction "C_3") (pintype "passive"))
    )
    (net (code "31") (name "Net-(K3_WA-P)") (class "Default")
      (node (ref "K3_W") (pin "4") (pinfunction "P_4") (pintype "passive"))
      (node (ref "R18") (pin "P$2") (pinfunction "P$2_P$2") (pintype "passive"))
    )
    (net (code "32") (name "Net-(K3_WC--)") (class "Default")
      (node (ref "D3") (pin "A") (pinfunction "A_A") (pintype "passive"))
      (node (ref "K3_W") (pin "7") (pinfunction "-_7") (pintype "passive"))
      (node (ref "Q1") (pin "3") (pinfunction "C_3") (pintype "passive"))
    )
    (net (code "33") (name "Net-(K3_WD--)") (class "Default")
      (node (ref "D4") (pin "A") (pinfunction "A_A") (pintype "passive"))
      (node (ref "K3_W") (pin "12") (pinfunction "-_12") (pintype "passive"))
      (node (ref "Q2") (pin "3") (pinfunction "C_3") (pintype "passive"))
    )
    (net (code "34") (name "Net-(L1-UN)") (class "Default")
      (node (ref "A1") (pin "FEED") (pinfunction "FEED_FEED") (pintype "bidirectional"))
      (node (ref "L1") (pin "1") (pinfunction "UN_1") (pintype "bidirectional"))
    )
    (net (code "35") (name "Net-(L2-Pad2)") (class "Default")
      (node (ref "L2") (pin "2") (pinfunction "2_2") (pintype "bidirectional"))
      (node (ref "L3") (pin "1") (pinfunction "1_1") (pintype "bidirectional"))
    )
    (net (code "36") (name "Net-(L4-VDD_PA)") (class "Default")
      (node (ref "C22") (pin "1") (pinfunction "1_1") (pintype "bidirectional"))
      (node (ref "L4") (pin "VCC") (pinfunction "VDD_PA_VCC") (pintype "bidirectional"))
      (node (ref "U10") (pin "30") (pinfunction "VDD_PA_30") (pintype "bidirectional"))
    )
    (net (code "37") (name "Net-(Q1-B)") (class "Default")
      (node (ref "Q1") (pin "1") (pinfunction "B_1") (pintype "passive"))
      (node (ref "R3") (pin "2") (pinfunction "2_2") (pintype "passive"))
      (node (ref "R9") (pin "2") (pinfunction "2_2") (pintype "passive"))
    )
    (net (code "38") (name "Net-(Q2-B)") (class "Default")
      (node (ref "Q2") (pin "1") (pinfunction "B_1") (pintype "passive"))
      (node (ref "R10") (pin "2") (pinfunction "2_2") (pintype "passive"))
      (node (ref "R4") (pin "2") (pinfunction "2_2") (pintype "passive"))
    )
    (net (code "39") (name "Net-(Q3-B)") (class "Default")
      (node (ref "Q3") (pin "1") (pinfunction "B_1") (pintype "passive"))
      (node (ref "R11") (pin "2") (pinfunction "2_2") (pintype "passive"))
      (node (ref "R5") (pin "2") (pinfunction "2_2") (pintype "passive"))
    )
    (net (code "40") (name "Net-(Q4-B)") (class "Default")
      (node (ref "Q4") (pin "1") (pinfunction "B_1") (pintype "passive"))
      (node (ref "R12") (pin "2") (pinfunction "2_2") (pintype "passive"))
      (node (ref "R6") (pin "2") (pinfunction "2_2") (pintype "passive"))
    )
    (net (code "41") (name "Net-(Q5-B)") (class "Default")
      (node (ref "Q5") (pin "1") (pinfunction "B_1") (pintype "passive"))
      (node (ref "R13") (pin "2") (pinfunction "2_2") (pintype "passive"))
      (node (ref "R7") (pin "2") (pinfunction "2_2") (pintype "passive"))
    )
    (net (code "42") (name "Net-(Q6-B)") (class "Default")
      (node (ref "Q6") (pin "1") (pinfunction "B_1") (pintype "passive"))
      (node (ref "R14") (pin "2") (pinfunction "2_2") (pintype "passive"))
      (node (ref "R8") (pin "2") (pinfunction "2_2") (pintype "passive"))
    )
    (net (code "43") (name "Net-(U1-AVDD)") (class "Default")
      (node (ref "C3") (pin "P$1") (pinfunction "P$1_P$1") (pintype "passive"))
      (node (ref "U1") (pin "5") (pinfunction "AVDD_5") (pintype "bidirectional"))
    )
    (net (code "44") (name "Net-(U1-DVDD)") (class "Default")
      (node (ref "C9") (pin "P$2") (pinfunction "P$2_P$2") (pintype "passive"))
      (node (ref "U1") (pin "21") (pinfunction "DVDD_21") (pintype "bidirectional"))
    )
    (net (code "45") (name "Net-(U1-RFN)") (class "Default")
      (node (ref "L1") (pin "3") (pinfunction "BAL_3") (pintype "bidirectional"))
      (node (ref "U1") (pin "13") (pinfunction "RFN_13") (pintype "bidirectional"))
    )
    (net (code "46") (name "Net-(U1-RFP)") (class "Default")
      (node (ref "L1") (pin "4") (pinfunction "BAL_4") (pintype "bidirectional"))
      (node (ref "U1") (pin "12") (pinfunction "RFP_12") (pintype "bidirectional"))
    )
    (net (code "47") (name "Net-(U1-VDDCORE)") (class "Default")
      (node (ref "C6") (pin "P$2") (pinfunction "P$2_P$2") (pintype "passive"))
      (node (ref "U1") (pin "29") (pinfunction "VDDCORE_29") (pintype "bidirectional"))
    )
    (net (code "48") (name "Net-(U1-XT1)") (class "Default")
      (node (ref "C1") (pin "P$2") (pinfunction "P$2_P$2") (pintype "passive"))
      (node (ref "U1") (pin "2") (pinfunction "XT1_2") (pintype "bidirectional"))
      (node (ref "X1") (pin "3") (pinfunction "X2_3") (pintype "power_in"))
    )
    (net (code "49") (name "Net-(U1-XT2)") (class "Default")
      (node (ref "C2") (pin "P$2") (pinfunction "P$2_P$2") (pintype "passive"))
      (node (ref "U1") (pin "1") (pinfunction "XT2_1") (pintype "bidirectional"))
      (node (ref "X1") (pin "1") (pinfunction "X1_1") (pintype "power_in"))
    )
    (net (code "50") (name "Net-(U4-X1)") (class "Default")
      (node (ref "C28") (pin "1") (pinfunction "1_1") (pintype "bidirectional"))
      (node (ref "U4") (pin "1") (pinfunction "X1_1") (pintype "bidirectional"))
      (node (ref "X4") (pin "A") (pinfunction "1_A") (pintype "bidirectional"))
    )
    (net (code "51") (name "Net-(U4-X2)") (class "Default")
      (node (ref "C29") (pin "1") (pinfunction "1_1") (pintype "bidirectional"))
      (node (ref "U4") (pin "2") (pinfunction "X2_2") (pintype "bidirectional"))
      (node (ref "X4") (pin "B") (pinfunction "2_B") (pintype "bidirectional"))
    )
    (net (code "52") (name "Net-(U6-VIN)") (class "Default")
      (node (ref "D13") (pin "C") (pinfunction "C_C") (pintype "passive"))
      (node (ref "R1") (pin "P$2") (pinfunction "P$2_P$2") (pintype "passive"))
      (node (ref "U6") (pin "3") (pinfunction "VIN_3") (pintype "bidirectional"))
    )
    (net (code "53") (name "Net-(U10-ANT1)") (class "Default")
      (node (ref "L4") (pin "ANT1") (pinfunction "ANT1_ANT1") (pintype "bidirectional"))
      (node (ref "U10") (pin "31") (pinfunction "ANT1_31") (pintype "bidirectional"))
    )
    (net (code "54") (name "Net-(U10-ANT2)") (class "Default")
      (node (ref "L4") (pin "ANT2") (pinfunction "ANT2_ANT2") (pintype "bidirectional"))
      (node (ref "U10") (pin "32") (pinfunction "ANT2_32") (pintype "bidirectional"))
    )
    (net (code "55") (name "Net-(U10-DCC)") (class "Default")
      (node (ref "L3") (pin "2") (pinfunction "2_2") (pintype "bidirectional"))
      (node (ref "U10") (pin "2") (pinfunction "DCC_2") (pintype "bidirectional"))
    )
    (net (code "56") (name "Net-(U10-DEC1)") (class "Default")
      (node (ref "C19") (pin "1") (pinfunction "1_1") (pintype "bidirectional"))
      (node (ref "U10") (pin "39") (pinfunction "DEC1_39") (pintype "bidirectional"))
    )
    (net (code "57") (name "Net-(U10-DEC2)") (class "Default")
      (node (ref "C18") (pin "1") (pinfunction "1_1") (pintype "bidirectional"))
      (node (ref "U10") (pin "29") (pinfunction "DEC2_29") (pintype "bidirectional"))
    )
    (net (code "58") (name "Net-(U10-P26{slash}AIN0{slash}XL2)") (class "Default")
      (node (ref "C20") (pin "1") (pinfunction "1_1") (pintype "bidirectional"))
      (node (ref "U10") (pin "45") (pinfunction "P26/AIN0/XL2_45") (pintype "bidirectional"))
      (node (ref "X3") (pin "A") (pinfunction "1_A") (pintype "bidirectional"))
    )
    (net (code "59") (name "Net-(U10-P27{slash}AIN1{slash}XL1)") (class "Default")
      (node (ref "C21") (pin "1") (pinfunction "1_1") (pintype "bidirectional"))
      (node (ref "U10") (pin "46") (pinfunction "P27/AIN1/XL1_46") (pintype "bidirectional"))
      (node (ref "X3") (pin "B") (pinfunction "2_B") (pintype "bidirectional"))
    )
    (net (code "60") (name "Net-(U10-XC1)") (class "Default")
      (node (ref "C16") (pin "1") (pinfunction "1_1") (pintype "bidirectional"))
      (node (ref "U10") (pin "37") (pinfunction "XC1_37") (pintype "bidirectional"))
      (node (ref "X2") (pin "1") (pinfunction "1_1") (pintype "bidirectional"))
    )
    (net (code "61") (name "Net-(U10-XC2)") (class "Default")
      (node (ref "C17") (pin "1") (pinfunction "1_1") (pintype "bidirectional"))
      (node (ref "U10") (pin "38") (pinfunction "XC2_38") (pintype "bidirectional"))
      (node (ref "X2") (pin "3") (pinfunction "2_3") (pintype "bidirectional"))
    )
    (net (code "62") (name "Net-(U11-RESET)") (class "Default")
      (node (ref "R16") (pin "2") (pinfunction "2_2") (pintype "passive"))
      (node (ref "U11") (pin "13") (pinfunction "RESET_13") (pintype "bidirectional"))
    )
    (net (code "63") (name "OOB") (class "Default")
      (node (ref "U$1") (pin "6") (pinfunction "TDO/SWO_6") (pintype "bidirectional"))
      (node (ref "U1") (pin "25") (pinfunction "PA27_25") (pintype "bidirectional"))
    )
    (net (code "64") (name "P08") (class "Default")
      (node (ref "U10") (pin "14") (pinfunction "P08_14") (pintype "bidirectional"))
    )
    (net (code "65") (name "P09") (class "Default")
      (node (ref "U10") (pin "15") (pinfunction "P09_15") (pintype "bidirectional"))
    )
    (net (code "66") (name "P10") (class "Default")
      (node (ref "U10") (pin "16") (pinfunction "P10_16") (pintype "bidirectional"))
    )
    (net (code "67") (name "P17") (class "Default")
      (node (ref "U10") (pin "25") (pinfunction "P17_25") (pintype "bidirectional"))
    )
    (net (code "68") (name "P21") (class "Default")
      (node (ref "U10") (pin "40") (pinfunction "P21_40") (pintype "bidirectional"))
    )
    (net (code "69") (name "P22") (class "Default")
      (node (ref "U10") (pin "41") (pinfunction "P22_41") (pintype "bidirectional"))
    )
    (net (code "70") (name "P23") (class "Default")
      (node (ref "U10") (pin "42") (pinfunction "P23_42") (pintype "bidirectional"))
    )
    (net (code "71") (name "PIRSIG") (class "Default")
      (node (ref "TP16") (pin "P$1") (pinfunction "P$1_P$1") (pintype "bidirectional"))
      (node (ref "U1") (pin "7") (pinfunction "PA06_7") (pintype "bidirectional"))
      (node (ref "U10") (pin "9") (pinfunction "P05/AIN6_9") (pintype "bidirectional"))
      (node (ref "U7") (pin "OUT") (pinfunction "OUT_OUT") (pintype "bidirectional"))
    )
    (net (code "72") (name "R") (class "Default")
      (node (ref "D10") (pin "C") (pinfunction "C_C") (pintype "passive"))
      (node (ref "D9") (pin "A") (pinfunction "A_A") (pintype "passive"))
      (node (ref "J2") (pin "P$2") (pinfunction "2_P$2") (pintype "bidirectional"))
      (node (ref "J2") (pin "P$3") (pinfunction "3_P$3") (pintype "bidirectional"))
      (node (ref "K1_G") (pin "4") (pinfunction "P_4") (pintype "passive"))
      (node (ref "K2_Y") (pin "9") (pinfunction "P_9") (pintype "passive"))
      (node (ref "K3_W") (pin "9") (pinfunction "P_9") (pintype "passive"))
      (node (ref "R17") (pin "P$1") (pinfunction "P$1_P$1") (pintype "passive"))
      (node (ref "R18") (pin "P$1") (pinfunction "P$1_P$1") (pintype "passive"))
    )
    (net (code "73") (name "SPI_MISO") (class "Default")
      (node (ref "TP21") (pin "P$1") (pinfunction "P$1_P$1") (pintype "bidirectional"))
      (node (ref "U1") (pin "10") (pinfunction "PA09_10") (pintype "bidirectional"))
      (node (ref "U10") (pin "48") (pinfunction "P29_48") (pintype "bidirectional"))
    )
    (net (code "74") (name "SPI_MOSI") (class "Default")
      (node (ref "TP20") (pin "P$1") (pinfunction "P$1_P$1") (pintype "bidirectional"))
      (node (ref "U1") (pin "9") (pinfunction "PA08_9") (pintype "bidirectional"))
      (node (ref "U10") (pin "3") (pinfunction "P30_3") (pintype "bidirectional"))
    )
    (net (code "75") (name "SPI_SCK") (class "Default")
      (node (ref "TP23") (pin "P$1") (pinfunction "P$1_P$1") (pintype "bidirectional"))
      (node (ref "U1") (pin "16") (pinfunction "PA15_16") (pintype "bidirectional"))
      (node (ref "U10") (pin "4") (pinfunction "P00/AREF0_4") (pintype "bidirectional"))
    )
    (net (code "76") (name "SS") (class "Default")
      (node (ref "TP22") (pin "P$1") (pinfunction "P$1_P$1") (pintype "bidirectional"))
      (node (ref "U1") (pin "15") (pinfunction "PA14_15") (pintype "bidirectional"))
      (node (ref "U10") (pin "47") (pinfunction "P28_47") (pintype "bidirectional"))
    )
    (net (code "77") (name "SWCLK") (class "Default")
      (node (ref "U$1") (pin "4") (pinfunction "TCK/SWCLK_4") (pintype "bidirectional"))
      (node (ref "U1") (pin "31") (pinfunction "PA30_31") (pintype "bidirectional"))
    )
    (net (code "78") (name "SWDCLK") (class "Default")
      (node (ref "J1") (pin "4") (pinfunction "SWDCLK_4") (pintype "bidirectional"))
      (node (ref "R15") (pin "2") (pinfunction "2_2") (pintype "passive"))
      (node (ref "U10") (pin "24") (pinfunction "SWDCLK_24") (pintype "bidirectional"))
    )
    (net (code "79") (name "SWDIO") (class "Default")
      (node (ref "U$1") (pin "2") (pinfunction "TMS/SWD_2") (pintype "bidirectional"))
      (node (ref "U1") (pin "32") (pinfunction "PA31_32") (pintype "bidirectional"))
    )
    (net (code "80") (name "SWDIO{slash}~{RESET}") (class "Default")
      (node (ref "J1") (pin "2") (pinfunction "SWDIO_2") (pintype "bidirectional"))
      (node (ref "U10") (pin "23") (pinfunction "SWDIO/~{RESET}_23") (pintype "bidirectional"))
    )
    (net (code "81") (name "W") (class "Default")
      (node (ref "J2") (pin "P$4") (pinfunction "4_P$4") (pintype "bidirectional"))
      (node (ref "K3_W") (pin "8") (pinfunction "S_8") (pintype "passive"))
    )
    (net (code "82") (name "WR") (class "Default")
      (node (ref "R3") (pin "1") (pinfunction "1_1") (pintype "passive"))
      (node (ref "U11") (pin "5") (pinfunction "IO1_5") (pintype "bidirectional"))
    )
    (net (code "83") (name "WS") (class "Default")
      (node (ref "R4") (pin "1") (pinfunction "1_1") (pintype "passive"))
      (node (ref "U11") (pin "4") (pinfunction "IO0_4") (pintype "bidirectional"))
    )
    (net (code "84") (name "Y") (class "Default")
      (node (ref "J2") (pin "P$5") (pinfunction "5_P$5") (pintype "bidirectional"))
      (node (ref "K2_Y") (pin "8") (pinfunction "S_8") (pintype "passive"))
    )
    (net (code "85") (name "YR") (class "Default")
      (node (ref "R5") (pin "1") (pinfunction "1_1") (pintype "passive"))
      (node (ref "U11") (pin "8") (pinfunction "IO3_8") (pintype "bidirectional"))
    )
    (net (code "86") (name "YS") (class "Default")
      (node (ref "R6") (pin "1") (pinfunction "1_1") (pintype "passive"))
      (node (ref "U11") (pin "7") (pinfunction "IO2_7") (pintype "bidirectional"))
    )
    (net (code "87") (name "unconnected-(D2-C-Pad3)") (class "Default")
      (node (ref "D2") (pin "3") (pinfunction "C_3") (pintype "passive"))
    )
    (net (code "88") (name "unconnected-(J1-SWO-Pad6)") (class "Default")
      (node (ref "J1") (pin "6") (pinfunction "SWO_6") (pintype "bidirectional"))
    )
    (net (code "89") (name "unconnected-(J1-~{RESET}-Pad3)") (class "Default")
      (node (ref "J1") (pin "3") (pinfunction "~{RESET}_3") (pintype "bidirectional"))
    )
    (net (code "90") (name "unconnected-(K1_GA-O-Pad3)") (class "Default")
      (node (ref "K1_G") (pin "3") (pinfunction "O_3") (pintype "passive"))
    )
    (net (code "91") (name "unconnected-(K1_GB-O-Pad10)") (class "Default")
      (node (ref "K1_G") (pin "10") (pinfunction "O_10") (pintype "passive"))
    )
    (net (code "92") (name "unconnected-(K1_GB-P-Pad9)") (class "Default")
      (node (ref "K1_G") (pin "9") (pinfunction "P_9") (pintype "passive"))
    )
    (net (code "93") (name "unconnected-(K1_GB-S-Pad8)") (class "Default")
      (node (ref "K1_G") (pin "8") (pinfunction "S_8") (pintype "passive"))
    )
    (net (code "94") (name "unconnected-(K2_YA-O-Pad3)") (class "Default")
      (node (ref "K2_Y") (pin "3") (pinfunction "O_3") (pintype "passive"))
    )
    (net (code "95") (name "unconnected-(K2_YB-O-Pad10)") (class "Default")
      (node (ref "K2_Y") (pin "10") (pinfunction "O_10") (pintype "passive"))
    )
    (net (code "96") (name "unconnected-(K3_WA-O-Pad3)") (class "Default")
      (node (ref "K3_W") (pin "3") (pinfunction "O_3") (pintype "passive"))
    )
    (net (code "97") (name "unconnected-(K3_WB-O-Pad10)") (class "Default")
      (node (ref "K3_W") (pin "10") (pinfunction "O_10") (pintype "passive"))
    )
    (net (code "98") (name "unconnected-(U1-PA28-Pad27)") (class "Default")
      (node (ref "U1") (pin "27") (pinfunction "PA28_27") (pintype "bidirectional"))
    )
    (net (code "99") (name "unconnected-(U4-MFP-Pad7)") (class "Default")
      (node (ref "U4") (pin "7") (pinfunction "MFP_7") (pintype "bidirectional"))
    )
    (net (code "100") (name "unconnected-(U5-NC-Pad1)") (class "Default")
      (node (ref "U5") (pin "1") (pinfunction "NC_1") (pintype "bidirectional"))
    )
    (net (code "101") (name "unconnected-(U5-NC-Pad2)") (class "Default")
      (node (ref "U5") (pin "2") (pinfunction "NC_2") (pintype "bidirectional"))
    )
    (net (code "102") (name "unconnected-(U8-IO3-Pad4)") (class "Default")
      (node (ref "U8") (pin "4") (pinfunction "IO3_4") (pintype "bidirectional"))
    )
    (net (code "103") (name "unconnected-(U8-IO4-Pad6)") (class "Default")
      (node (ref "U8") (pin "6") (pinfunction "IO4_6") (pintype "bidirectional"))
    )
    (net (code "104") (name "unconnected-(U10-P14-Pad20)") (class "Default")
      (node (ref "U10") (pin "20") (pinfunction "P14_20") (pintype "bidirectional"))
    )
    (net (code "105") (name "unconnected-(U10-P15-Pad21)") (class "Default")
      (node (ref "U10") (pin "21") (pinfunction "P15_21") (pintype "bidirectional"))
    )
    (net (code "106") (name "unconnected-(U10-P16-Pad22)") (class "Default")
      (node (ref "U10") (pin "22") (pinfunction "P16_22") (pintype "bidirectional"))
    )
    (net (code "107") (name "unconnected-(U10-P20-Pad28)") (class "Default")
      (node (ref "U10") (pin "28") (pinfunction "P20_28") (pintype "bidirectional"))
    )
    (net (code "108") (name "unconnected-(U11-IO6-Pad11)") (class "Default")
      (node (ref "U11") (pin "11") (pinfunction "IO6_11") (pintype "bidirectional"))
    )
    (net (code "109") (name "unconnected-(U11-IO7-Pad12)") (class "Default")
      (node (ref "U11") (pin "12") (pinfunction "IO7_12") (pintype "bidirectional"))
    )
    (net (code "110") (name "~{RESET}") (class "Default")
      (node (ref "U$1") (pin "3") (pinfunction "~{RST}_3") (pintype "bidirectional"))
      (node (ref "U1") (pin "26") (pinfunction "~{RESET}_26") (pintype "bidirectional"))
    )
  )
)
